# CrowPanel_ESP32_Display-5_0-inch-V3_0-20.net
KiCad netlist of a schematic drawn in EAGLE
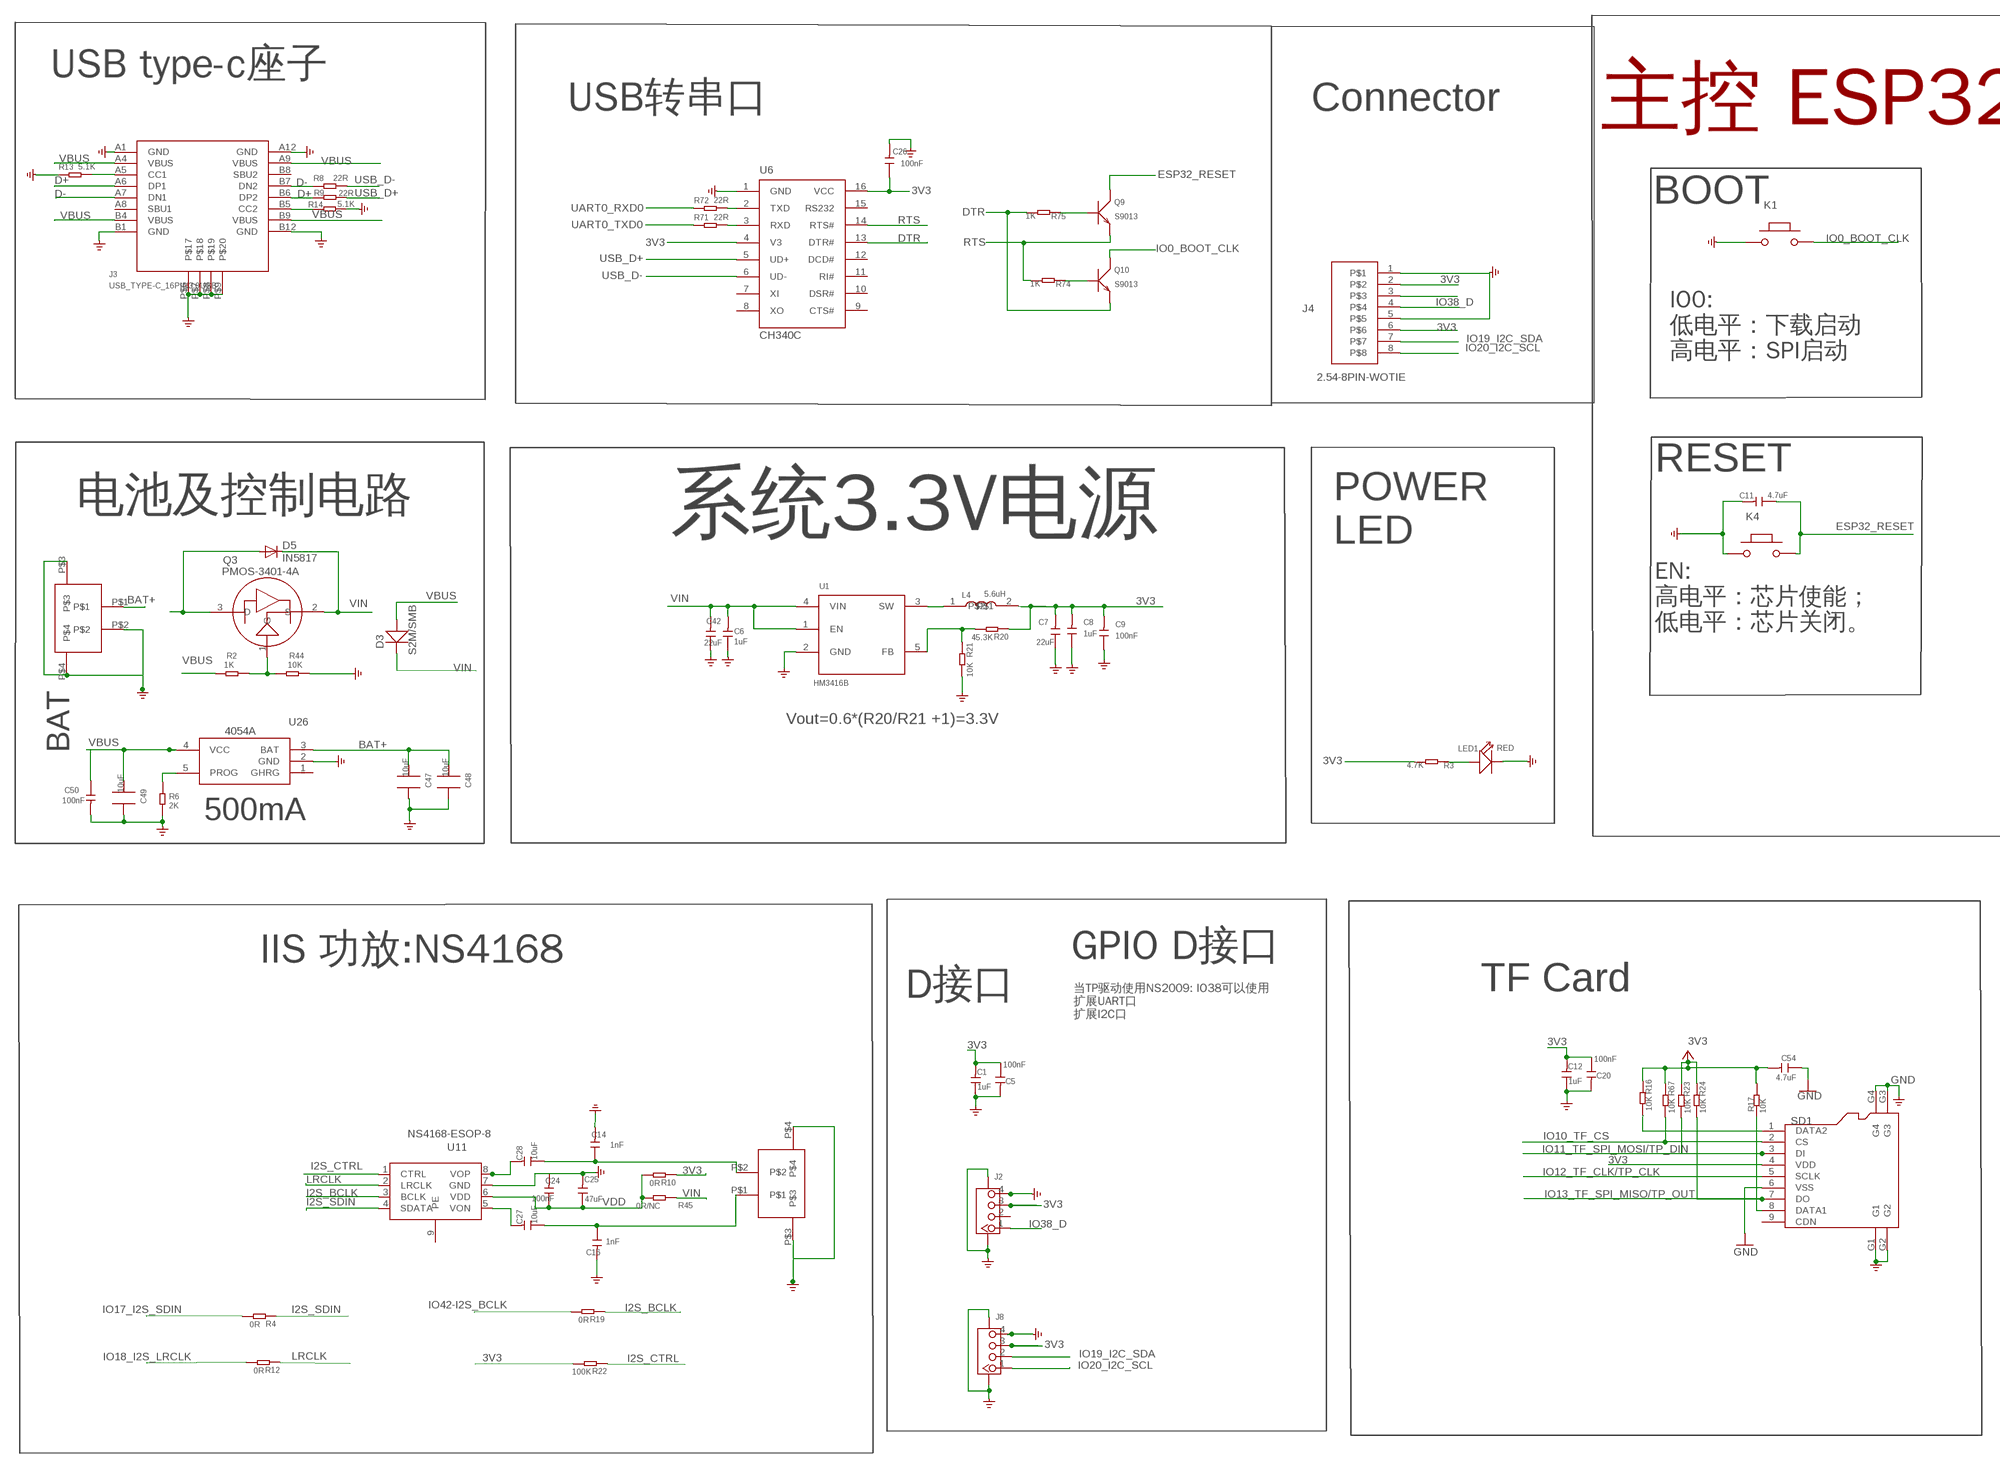
[diagram p0: schematic, sheet 1, part 1 of 2]
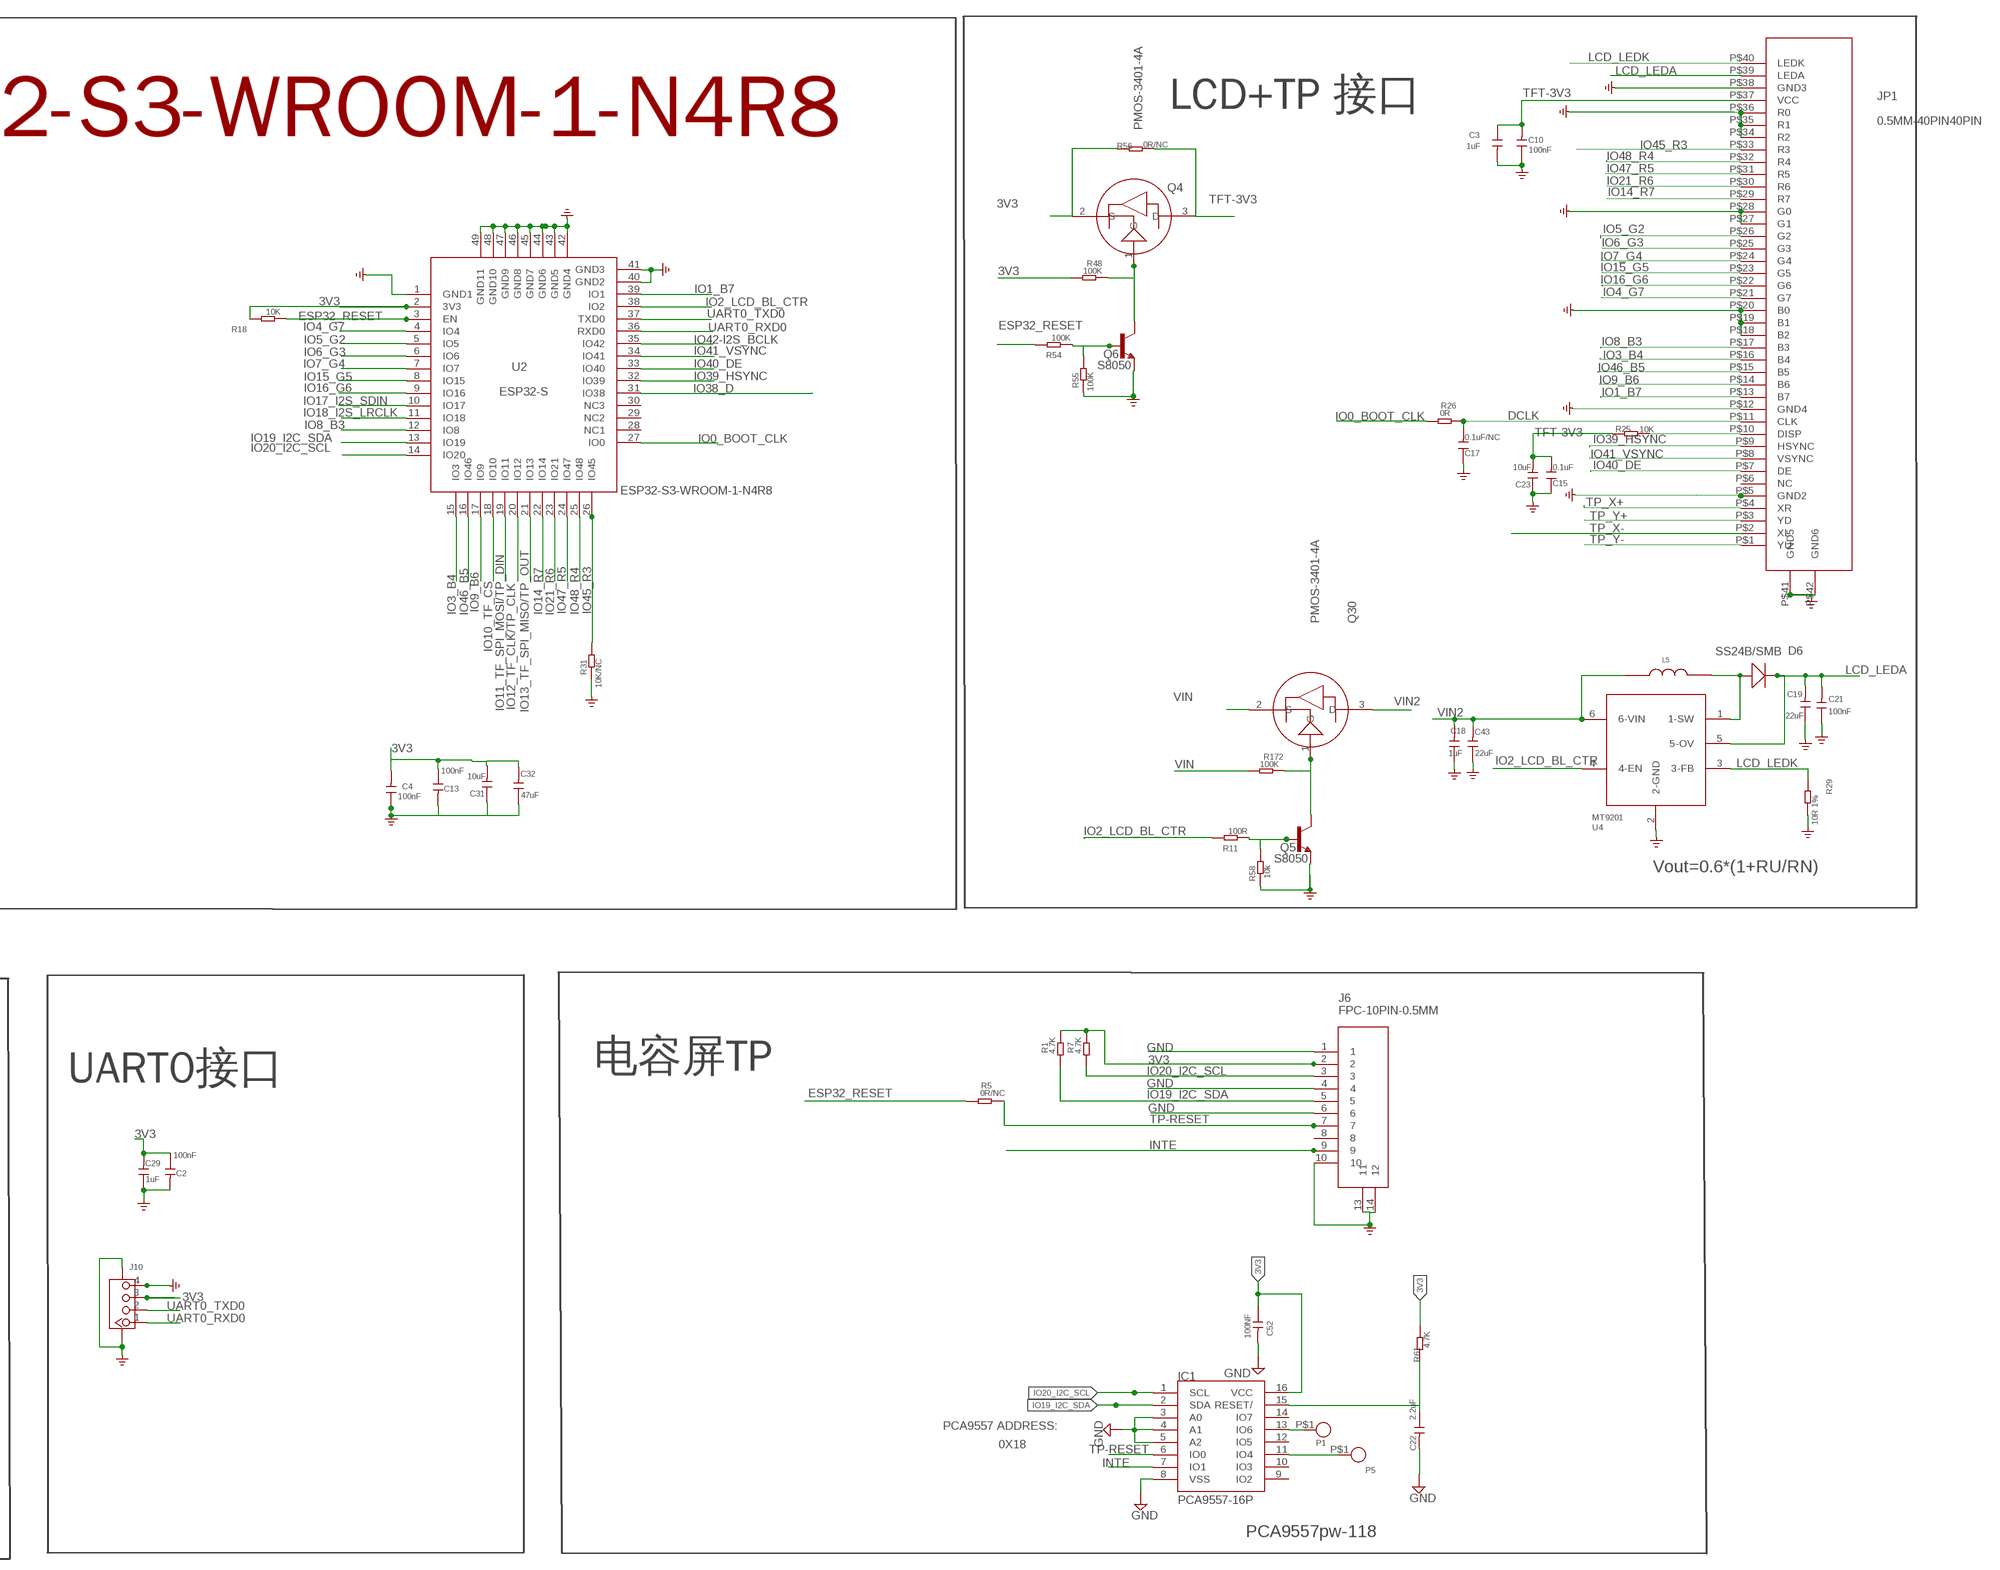
[diagram p1: schematic, sheet 1, part 2 of 2]

(export (version "E")
  (design (tool "Eeschema 10.0.6"))
  (components
    (comp (ref "C1")
      (value "1uF")
      (footprint "eagle-import:DISCRETE_C0603")
      (libsource (lib "eagle-import") (part "A_xbj_DISCRETE_C-0603"))
    )
    (comp (ref "C2")
      (value "100nF")
      (footprint "eagle-import:C0603")
      (libsource (lib "eagle-import") (part "C-0603"))
    )
    (comp (ref "C3")
      (value "1uF")
      (footprint "eagle-import:C0603")
      (libsource (lib "eagle-import") (part "C-0603"))
    )
    (comp (ref "C4")
      (value "100nF")
      (footprint "eagle-import:C0603")
      (libsource (lib "eagle-import") (part "C-0603"))
    )
    (comp (ref "C5")
      (value "100nF")
      (footprint "eagle-import:C0603")
      (libsource (lib "eagle-import") (part "C-0603"))
    )
    (comp (ref "C6")
      (value "1uF")
      (footprint "eagle-import:0603")
      (libsource (lib "eagle-import") (part "C0603"))
    )
    (comp (ref "C7")
      (value "22uF")
      (footprint "eagle-import:0805")
      (libsource (lib "eagle-import") (part "C0805"))
    )
    (comp (ref "C8")
      (value "1uF")
      (footprint "eagle-import:0603")
      (libsource (lib "eagle-import") (part "C0603"))
    )
    (comp (ref "C9")
      (value "100nF")
      (footprint "eagle-import:0603")
      (libsource (lib "eagle-import") (part "C0603"))
    )
    (comp (ref "C10")
      (value "100nF")
      (footprint "eagle-import:C0603")
      (libsource (lib "eagle-import") (part "C-0603"))
    )
    (comp (ref "C11")
      (value "4.7uF")
      (footprint "eagle-import:0603")
      (libsource (lib "eagle-import") (part "C0603"))
    )
    (comp (ref "C12")
      (value "1uF")
      (footprint "eagle-import:DISCRETE_C0603")
      (libsource (lib "eagle-import") (part "A_xbj_DISCRETE_C-0603"))
    )
    (comp (ref "C13")
      (value "100nF")
      (footprint "eagle-import:C0603")
      (libsource (lib "eagle-import") (part "C-0603"))
    )
    (comp (ref "C14")
      (value "1nF")
      (footprint "eagle-import:C0603")
      (libsource (lib "eagle-import") (part "C-0603"))
    )
    (comp (ref "C15")
      (value "0.1uF")
      (footprint "eagle-import:DISCRETE_C0603")
      (libsource (lib "eagle-import") (part "DISCRETE_C-0603"))
    )
    (comp (ref "C16")
      (value "1nF")
      (footprint "eagle-import:C0603")
      (libsource (lib "eagle-import") (part "C-0603"))
    )
    (comp (ref "C17")
      (value "0.1uF/NC")
      (footprint "eagle-import:DISCRETE_C0603")
      (libsource (lib "eagle-import") (part "DISCRETE_C-0603"))
    )
    (comp (ref "C18")
      (value "1uF")
      (footprint "eagle-import:0603")
      (libsource (lib "eagle-import") (part "C0603"))
    )
    (comp (ref "C19")
      (value "22uF")
      (footprint "eagle-import:0805")
      (libsource (lib "eagle-import") (part "C0805"))
    )
    (comp (ref "C20")
      (value "100nF")
      (footprint "eagle-import:C0603")
      (libsource (lib "eagle-import") (part "C-0603"))
    )
    (comp (ref "C21")
      (value "100nF")
      (footprint "eagle-import:0603")
      (libsource (lib "eagle-import") (part "C0603"))
    )
    (comp (ref "C22")
      (value "2.2uF")
      (footprint "eagle-import:0603")
      (libsource (lib "eagle-import") (part "C0603"))
    )
    (comp (ref "C23")
      (value "10uF")
      (footprint "eagle-import:DISCRETE_C0603")
      (libsource (lib "eagle-import") (part "DISCRETE_C-0603"))
    )
    (comp (ref "C24")
      (value "100nF")
      (footprint "eagle-import:C0603")
      (libsource (lib "eagle-import") (part "C-0603"))
    )
    (comp (ref "C25")
      (value "47uF")
      (footprint "eagle-import:0805")
      (libsource (lib "eagle-import") (part "C0805"))
    )
    (comp (ref "C26")
      (value "100nF")
      (footprint "eagle-import:0603")
      (libsource (lib "eagle-import") (part "C0603"))
    )
    (comp (ref "C27")
      (value "10uF")
      (footprint "eagle-import:DISCRETE_C0603")
      (libsource (lib "eagle-import") (part "A_xbj_DISCRETE_C-0603"))
    )
    (comp (ref "C28")
      (value "10uF")
      (footprint "eagle-import:DISCRETE_C0603")
      (libsource (lib "eagle-import") (part "A_xbj_DISCRETE_C-0603"))
    )
    (comp (ref "C29")
      (value "1uF")
      (footprint "eagle-import:DISCRETE_C0603")
      (libsource (lib "eagle-import") (part "A_xbj_DISCRETE_C-0603"))
    )
    (comp (ref "C31")
      (value "10uF")
      (footprint "eagle-import:DISCRETE_C0603")
      (libsource (lib "eagle-import") (part "DISCRETE_C-0603"))
    )
    (comp (ref "C32")
      (value "47uF")
      (footprint "eagle-import:0805")
      (libsource (lib "eagle-import") (part "C0805"))
    )
    (comp (ref "C42")
      (value "22uF")
      (footprint "eagle-import:0805")
      (libsource (lib "eagle-import") (part "C0805"))
    )
    (comp (ref "C43")
      (value "22uF")
      (footprint "eagle-import:0805")
      (libsource (lib "eagle-import") (part "C0805"))
    )
    (comp (ref "C47")
      (value "10uF")
      (footprint "eagle-import:0805_S")
      (libsource (lib "eagle-import") (part "C0805_S"))
    )
    (comp (ref "C48")
      (value "10uF")
      (footprint "eagle-import:0805_S")
      (libsource (lib "eagle-import") (part "C0805_S"))
    )
    (comp (ref "C49")
      (value "10uF")
      (footprint "eagle-import:0805_S")
      (libsource (lib "eagle-import") (part "C0805_S"))
    )
    (comp (ref "C50")
      (value "100nF")
      (footprint "eagle-import:C0603")
      (libsource (lib "eagle-import") (part "C-0603"))
    )
    (comp (ref "C52")
      (value "100NF")
      (footprint "eagle-import:A_XBJ_0603")
      (libsource (lib "eagle-import") (part "A_XBJ_C0603"))
    )
    (comp (ref "C54")
      (value "4.7uF")
      (footprint "eagle-import:DISCRETE_C0603")
      (libsource (lib "eagle-import") (part "DISCRETE_C-0603"))
    )
    (comp (ref "D3")
      (value "S2M/SMB")
      (footprint "eagle-import:214AB")
      (libsource (lib "eagle-import") (part "214ABDO-214AB"))
    )
    (comp (ref "D5")
      (value "IN5817")
      (footprint "eagle-import:DO-214AC")
      (libsource (lib "eagle-import") (part "DIODE-DO-214AC"))
    )
    (comp (ref "D6")
      (value "SS24B/SMB")
      (footprint "eagle-import:214AB")
      (libsource (lib "eagle-import") (part "214ABDO-214AB"))
    )
    (comp (ref "IC1")
      (value "PCA9557-16P")
      (footprint "eagle-import:TSSOP16")
      (libsource (lib "eagle-import") (part "PCA9557-16P"))
    )
    (comp (ref "J1")
      (value "PH2.0WT-2PIN")
      (footprint "eagle-import:PH2.0WT-2PIN")
      (libsource (lib "eagle-import") (part "PH2.0WT-2PIN"))
    )
    (comp (ref "J2")
      (value "CONNECTOR_TWIG-4P-2.0-SMD-FEMALE-REINFORCE90D")
      (footprint "eagle-import:CONNECTOR_4P-SMD-2.0-90D")
      (libsource (lib "eagle-import") (part "CONNECTOR_TWIG-4P-2.0-SMD-FEMALE-REINFORCE90D"))
    )
    (comp (ref "J3")
      (value "USB_TYPE-C_16PIN3.0USB")
      (footprint "eagle-import:KEVIN_3.0TYPEC-SMD")
      (libsource (lib "eagle-import") (part "USB_TYPE-C_16PIN3.0USB"))
    )
    (comp (ref "J4")
      (value "2.54-8PIN-WOTIE")
      (footprint "eagle-import:2.54-8P-WOTIE")
      (libsource (lib "eagle-import") (part "2.54-8PIN-WOTIE"))
    )
    (comp (ref "J5")
      (value "PH2.0WT-2PIN")
      (footprint "eagle-import:PH2.0WT-2PIN")
      (libsource (lib "eagle-import") (part "PH2.0WT-2PIN"))
    )
    (comp (ref "J6")
      (value "FPC-10PIN-0.5MM")
      (footprint "eagle-import:FPC-10PIN-0.5MM")
      (libsource (lib "eagle-import") (part "FPC-10PIN-0.5MM"))
    )
    (comp (ref "J8")
      (value "CONNECTOR_TWIG-4P-2.0-SMD-FEMALE-REINFORCE90D")
      (footprint "eagle-import:CONNECTOR_4P-SMD-2.0-90D")
      (libsource (lib "eagle-import") (part "CONNECTOR_TWIG-4P-2.0-SMD-FEMALE-REINFORCE90D"))
    )
    (comp (ref "J10")
      (value "CONNECTOR_TWIG-4P-2.0-SMD-FEMALE-REINFORCE90D")
      (footprint "eagle-import:CONNECTOR_4P-SMD-2.0-90D")
      (libsource (lib "eagle-import") (part "CONNECTOR_TWIG-4P-2.0-SMD-FEMALE-REINFORCE90D"))
    )
    (comp (ref "JP1")
      (value "0.5MM-40PIN40PIN")
      (footprint "eagle-import:0.5MM_40P")
      (libsource (lib "eagle-import") (part "0.5MM-40PIN40PIN"))
    )
    (comp (ref "K1")
      (value "BUTTON")
      (footprint "eagle-import:157SW")
      (libsource (lib "eagle-import") (part "PB157"))
    )
    (comp (ref "K4")
      (value "BUTTON")
      (footprint "eagle-import:157SW")
      (libsource (lib "eagle-import") (part "PB157"))
    )
    (comp (ref "L4")
      (value "5.6uH")
      (footprint "eagle-import:CD54_CD54")
      (libsource (lib "eagle-import") (part "L-0530"))
    )
    (comp (ref "L5")
      (value "CD32_6.8uH")
      (footprint "eagle-import:CD32")
      (libsource (lib "eagle-import") (part "CD32_950MA"))
    )
    (comp (ref "LED1")
      (value "RED")
      (footprint "eagle-import:DISCRETE_LED-0603")
      (libsource (lib "eagle-import") (part "DISCRETE_LED0603"))
    )
    (comp (ref "P1")
      (value "CROWPI_POW_PADPAD-1.0MM")
      (footprint "eagle-import:CROWPI_POW_PAD-1.0MM")
      (libsource (lib "eagle-import") (part "CROWPI_POW_PADPAD-1.0MM"))
    )
    (comp (ref "P5")
      (value "CROWPI_POW_PADPAD-1.0MM")
      (footprint "eagle-import:CROWPI_POW_PAD-1.0MM")
      (libsource (lib "eagle-import") (part "CROWPI_POW_PADPAD-1.0MM"))
    )
    (comp (ref "Q3")
      (value "PMOS-3401-4A")
      (footprint "eagle-import:SOT-23")
      (libsource (lib "eagle-import") (part "P-MOS-SOT23"))
    )
    (comp (ref "Q4")
      (value "PMOS-3401-4A")
      (footprint "eagle-import:SOT-23")
      (libsource (lib "eagle-import") (part "P-MOS-SOT23"))
    )
    (comp (ref "Q5")
      (value "S8050")
      (footprint "eagle-import:SPARKFUN_SOT23")
      (libsource (lib "eagle-import") (part "SPARKFUN_TRANSISTOR_NPNSOT23"))
    )
    (comp (ref "Q6")
      (value "S8050")
      (footprint "eagle-import:SPARKFUN_SOT23")
      (libsource (lib "eagle-import") (part "SPARKFUN_TRANSISTOR_NPNSOT23"))
    )
    (comp (ref "Q9")
      (value "S9013")
      (footprint "eagle-import:SOT23@1")
      (libsource (lib "eagle-import") (part "TRANSISTOR-NPN-SOT23"))
    )
    (comp (ref "Q10")
      (value "S9013")
      (footprint "eagle-import:SOT23@1")
      (libsource (lib "eagle-import") (part "TRANSISTOR-NPN-SOT23"))
    )
    (comp (ref "Q30")
      (value "PMOS-3401-4A")
      (footprint "eagle-import:SOT-23")
      (libsource (lib "eagle-import") (part "P-MOS-SOT23"))
    )
    (comp (ref "R1")
      (value "4.7K")
      (footprint "eagle-import:R0603")
      (libsource (lib "eagle-import") (part "R-0603"))
    )
    (comp (ref "R2")
      (value "1K")
      (footprint "eagle-import:DISCRETE_R0603")
      (libsource (lib "eagle-import") (part "DISCRETE_R-0603"))
    )
    (comp (ref "R3")
      (value "4.7K")
      (footprint "eagle-import:DISCRETE_R0603")
      (libsource (lib "eagle-import") (part "Crowtail-_LED-V2.0-20190615-01_DISCRETE_R-0603"))
    )
    (comp (ref "R4")
      (value "0R")
      (footprint "eagle-import:DISCRETE_R0603")
      (libsource (lib "eagle-import") (part "Crowtail-_LED-V2.0-20190615-01_DISCRETE_R-0603"))
    )
    (comp (ref "R5")
      (value "0R/NC")
      (footprint "eagle-import:R0603")
      (libsource (lib "eagle-import") (part "R-0603"))
    )
    (comp (ref "R6")
      (value "2K")
      (footprint "eagle-import:DISCRETE_R0603")
      (libsource (lib "eagle-import") (part "DISCRETE_R-0603"))
    )
    (comp (ref "R7")
      (value "4.7K")
      (footprint "eagle-import:R0603")
      (libsource (lib "eagle-import") (part "R-0603"))
    )
    (comp (ref "R8")
      (value "22R")
      (footprint "eagle-import:DISCRETE_R0603")
      (libsource (lib "eagle-import") (part "Crowtail-_LED-V2.0-20190615-01_DISCRETE_R-0603"))
    )
    (comp (ref "R9")
      (value "22R")
      (footprint "eagle-import:DISCRETE_R0603")
      (libsource (lib "eagle-import") (part "Crowtail-_LED-V2.0-20190615-01_DISCRETE_R-0603"))
    )
    (comp (ref "R10")
      (value "0R")
      (footprint "eagle-import:DISCRETE_R0603")
      (libsource (lib "eagle-import") (part "Crowtail-_LED-V2.0-20190615-01_DISCRETE_R-0603"))
    )
    (comp (ref "R11")
      (value "100R")
      (footprint "eagle-import:R0603")
      (libsource (lib "eagle-import") (part "R0603"))
    )
    (comp (ref "R12")
      (value "0R")
      (footprint "eagle-import:DISCRETE_R0603")
      (libsource (lib "eagle-import") (part "Crowtail-_LED-V2.0-20190615-01_DISCRETE_R-0603"))
    )
    (comp (ref "R13")
      (value "5.1K")
      (footprint "eagle-import:DISCRETE_R0603")
      (libsource (lib "eagle-import") (part "Crowtail-_LED-V2.0-20190615-01_DISCRETE_R-0603"))
    )
    (comp (ref "R14")
      (value "5.1K")
      (footprint "eagle-import:DISCRETE_R0603")
      (libsource (lib "eagle-import") (part "Crowtail-_LED-V2.0-20190615-01_DISCRETE_R-0603"))
    )
    (comp (ref "R16")
      (value "10K")
      (footprint "eagle-import:DISCRETE_R0603")
      (libsource (lib "eagle-import") (part "Crowtail-_LED-V2.0-20190615-01_DISCRETE_R-0603"))
    )
    (comp (ref "R17")
      (value "10K")
      (footprint "eagle-import:DISCRETE_R0603")
      (libsource (lib "eagle-import") (part "Crowtail-_LED-V2.0-20190615-01_DISCRETE_R-0603"))
    )
    (comp (ref "R18")
      (value "10K")
      (footprint "eagle-import:DISCRETE_R0603")
      (libsource (lib "eagle-import") (part "Crowtail-_LED-V2.0-20190615-01_DISCRETE_R-0603"))
    )
    (comp (ref "R19")
      (value "0R")
      (footprint "eagle-import:DISCRETE_R0603")
      (libsource (lib "eagle-import") (part "Crowtail-_LED-V2.0-20190615-01_DISCRETE_R-0603"))
    )
    (comp (ref "R20")
      (value "45.3K")
      (footprint "eagle-import:DISCRETE_R0603")
      (libsource (lib "eagle-import") (part "Crowtail-_LED-V2.0-20190615-01_DISCRETE_R-0603"))
    )
    (comp (ref "R21")
      (value "10K")
      (footprint "eagle-import:DISCRETE_R0603")
      (libsource (lib "eagle-import") (part "Crowtail-_LED-V2.0-20190615-01_DISCRETE_R-0603"))
    )
    (comp (ref "R22")
      (value "100K")
      (footprint "eagle-import:DISCRETE_R0603")
      (libsource (lib "eagle-import") (part "Crowtail-_LED-V2.0-20190615-01_DISCRETE_R-0603"))
    )
    (comp (ref "R23")
      (value "10K")
      (footprint "eagle-import:DISCRETE_R0603")
      (libsource (lib "eagle-import") (part "Crowtail-_LED-V2.0-20190615-01_DISCRETE_R-0603"))
    )
    (comp (ref "R24")
      (value "10K")
      (footprint "eagle-import:DISCRETE_R0603")
      (libsource (lib "eagle-import") (part "Crowtail-_LED-V2.0-20190615-01_DISCRETE_R-0603"))
    )
    (comp (ref "R25")
      (value "10K")
      (footprint "eagle-import:DISCRETE_R0603")
      (libsource (lib "eagle-import") (part "Crowtail-_LED-V2.0-20190615-01_DISCRETE_R-0603"))
    )
    (comp (ref "R26")
      (value "0R")
      (footprint "eagle-import:R0603")
      (libsource (lib "eagle-import") (part "R-0603"))
    )
    (comp (ref "R29")
      (value "10R 1%")
      (footprint "eagle-import:DISCRETE_R0603")
      (libsource (lib "eagle-import") (part "Crowtail-_LED-V2.0-20190615-01_DISCRETE_R-0603"))
    )
    (comp (ref "R31")
      (value "10K/NC")
      (footprint "eagle-import:R0603")
      (libsource (lib "eagle-import") (part "R0603"))
    )
    (comp (ref "R44")
      (value "10K")
      (footprint "eagle-import:DISCRETE_R0603")
      (libsource (lib "eagle-import") (part "DISCRETE_R-0603"))
    )
    (comp (ref "R45")
      (value "0R/NC")
      (footprint "eagle-import:DISCRETE_R0603")
      (libsource (lib "eagle-import") (part "Crowtail-_LED-V2.0-20190615-01_DISCRETE_R-0603"))
    )
    (comp (ref "R48")
      (value "100K")
      (footprint "eagle-import:R0603")
      (libsource (lib "eagle-import") (part "R-0603"))
    )
    (comp (ref "R54")
      (value "100K")
      (footprint "eagle-import:R0603")
      (libsource (lib "eagle-import") (part "R0603"))
    )
    (comp (ref "R55")
      (value "100K")
      (footprint "eagle-import:R0603")
      (libsource (lib "eagle-import") (part "R0603"))
    )
    (comp (ref "R56")
      (value "0R/NC")
      (footprint "eagle-import:DISCRETE_R0603")
      (libsource (lib "eagle-import") (part "Crowtail-_LED-V2.0-20190615-01_DISCRETE_R-0603"))
    )
    (comp (ref "R58")
      (value "10k")
      (footprint "eagle-import:R0603")
      (libsource (lib "eagle-import") (part "R0603"))
    )
    (comp (ref "R61")
      (value "4.7K")
      (footprint "eagle-import:DISCRETE_R0603")
      (libsource (lib "eagle-import") (part "Lora_RA-08H_Dev_DISCRETE_R-0603"))
    )
    (comp (ref "R67")
      (value "10K")
      (footprint "eagle-import:DISCRETE_R0603")
      (libsource (lib "eagle-import") (part "Crowtail-_LED-V2.0-20190615-01_DISCRETE_R-0603"))
    )
    (comp (ref "R71")
      (value "22R")
      (footprint "eagle-import:DISCRETE_R0603")
      (libsource (lib "eagle-import") (part "Crowtail-_LED-V2.0-20190615-01_DISCRETE_R-0603"))
    )
    (comp (ref "R72")
      (value "22R")
      (footprint "eagle-import:DISCRETE_R0603")
      (libsource (lib "eagle-import") (part "Crowtail-_LED-V2.0-20190615-01_DISCRETE_R-0603"))
    )
    (comp (ref "R74")
      (value "1K")
      (footprint "eagle-import:DISCRETE_R0603")
      (libsource (lib "eagle-import") (part "Crowtail-_LED-V2.0-20190615-01_DISCRETE_R-0603"))
    )
    (comp (ref "R75")
      (value "1K")
      (footprint "eagle-import:DISCRETE_R0603")
      (libsource (lib "eagle-import") (part "Crowtail-_LED-V2.0-20190615-01_DISCRETE_R-0603"))
    )
    (comp (ref "R172")
      (value "100K")
      (footprint "eagle-import:R0603")
      (libsource (lib "eagle-import") (part "R-0603"))
    )
    (comp (ref "SD1")
      (value "HOLDER-MICROSD-9P")
      (footprint "eagle-import:9P-SMD-W_-RING")
      (libsource (lib "eagle-import") (part "HOLDER-MICROSD-9P"))
    )
    (comp (ref "U1")
      (value "HM3416B")
      (footprint "eagle-import:A_XBJ_SOT23-5")
      (libsource (lib "eagle-import") (part "A_XBJ_HM3420B"))
    )
    (comp (ref "U2")
      (value "ESP32-S")
      (footprint "eagle-import:ESP32-S3")
      (fields (field (name "U2") "ESP32-S3-WROOM-1-N4R8"))
      (libsource (lib "eagle-import") (part "ESP32-S"))
    )
    (comp (ref "U4")
      (value "MT9201")
      (footprint "eagle-import:SOT23-6")
      (libsource (lib "eagle-import") (part "MT9201"))
    )
    (comp (ref "U6")
      (value "CH340C")
      (footprint "eagle-import:SOP-16")
      (libsource (lib "eagle-import") (part "CH340G"))
    )
    (comp (ref "U11")
      (value "NS4168-ESOP-8")
      (footprint "eagle-import:NS4168-ESOP-8")
      (libsource (lib "eagle-import") (part "NS4168-ESOP-8"))
    )
    (comp (ref "U26")
      (value "4054A")
      (footprint "eagle-import:SOP23-5")
      (libsource (lib "eagle-import") (part "4054A"))
    )
  )
  (nets
    (net (code "1") (name "/BAT+") (class "Default")
      (node (ref "C47") (pin "2") (pinfunction "2_2") (pintype "bidirectional"))
      (node (ref "C48") (pin "2") (pinfunction "2_2") (pintype "bidirectional"))
      (node (ref "D5") (pin "A") (pinfunction "A_A") (pintype "passive"))
      (node (ref "J1") (pin "P$1") (pinfunction "P$1_P$1") (pintype "bidirectional"))
      (node (ref "Q3") (pin "3") (pinfunction "D_3") (pintype "bidirectional"))
      (node (ref "U26") (pin "3") (pinfunction "BAT_3") (pintype "bidirectional"))
    )
    (net (code "2") (name "/D+") (class "Default")
      (node (ref "J3") (pin "A6") (pinfunction "DP1_A6") (pintype "bidirectional"))
      (node (ref "J3") (pin "B6") (pinfunction "DP2_B6") (pintype "bidirectional"))
      (node (ref "R9") (pin "1") (pinfunction "1_1") (pintype "passive"))
    )
    (net (code "3") (name "/D-") (class "Default")
      (node (ref "J3") (pin "A7") (pinfunction "DN1_A7") (pintype "bidirectional"))
      (node (ref "J3") (pin "B7") (pinfunction "DN2_B7") (pintype "bidirectional"))
      (node (ref "R8") (pin "1") (pinfunction "1_1") (pintype "passive"))
    )
    (net (code "4") (name "/DCLK") (class "Default")
      (node (ref "C17") (pin "2") (pinfunction "2_2") (pintype "passive"))
      (node (ref "JP1") (pin "P$11") (pinfunction "CLK_P$11") (pintype "bidirectional"))
      (node (ref "R26") (pin "2") (pinfunction "2_2") (pintype "passive"))
    )
    (net (code "5") (name "/DTR") (class "Default")
      (node (ref "Q10") (pin "2") (pinfunction "E_2") (pintype "passive"))
      (node (ref "R75") (pin "2") (pinfunction "2_2") (pintype "passive"))
      (node (ref "U6") (pin "13") (pinfunction "DTR#_13") (pintype "bidirectional"))
    )
    (net (code "6") (name "/ESP32_RESET") (class "Default")
      (node (ref "C11") (pin "1") (pinfunction "1_1") (pintype "passive"))
      (node (ref "K4") (pin "2") (pinfunction "2_2") (pintype "passive"))
      (node (ref "Q9") (pin "3") (pinfunction "C_3") (pintype "passive"))
      (node (ref "R18") (pin "2") (pinfunction "2_2") (pintype "passive"))
      (node (ref "R5") (pin "1") (pinfunction "1_1") (pintype "passive"))
      (node (ref "R54") (pin "2") (pinfunction "2_2") (pintype "passive"))
      (node (ref "U2") (pin "3") (pinfunction "EN_3") (pintype "bidirectional"))
    )
    (net (code "7") (name "/I2S_BCLK") (class "Default")
      (node (ref "R19") (pin "1") (pinfunction "1_1") (pintype "passive"))
      (node (ref "U11") (pin "3") (pinfunction "BCLK_3") (pintype "bidirectional"))
    )
    (net (code "8") (name "/I2S_CTRL") (class "Default")
      (node (ref "R22") (pin "1") (pinfunction "1_1") (pintype "passive"))
      (node (ref "U11") (pin "1") (pinfunction "CTRL_1") (pintype "bidirectional"))
    )
    (net (code "9") (name "/I2S_SDIN") (class "Default")
      (node (ref "R4") (pin "1") (pinfunction "1_1") (pintype "passive"))
      (node (ref "U11") (pin "4") (pinfunction "SDATA_4") (pintype "bidirectional"))
    )
    (net (code "10") (name "/INTE") (class "Default")
      (node (ref "IC1") (pin "7") (pinfunction "IO1_7") (pintype "bidirectional"))
      (node (ref "J6") (pin "9") (pinfunction "9_9") (pintype "bidirectional"))
    )
    (net (code "11") (name "/IO0_BOOT_CLK") (class "Default")
      (node (ref "K1") (pin "2") (pinfunction "2_2") (pintype "passive"))
      (node (ref "Q10") (pin "3") (pinfunction "C_3") (pintype "passive"))
      (node (ref "R26") (pin "1") (pinfunction "1_1") (pintype "passive"))
      (node (ref "U2") (pin "27") (pinfunction "IO0_27") (pintype "bidirectional"))
    )
    (net (code "12") (name "/IO1_B7") (class "Default")
      (node (ref "JP1") (pin "P$13") (pinfunction "B7_P$13") (pintype "bidirectional"))
      (node (ref "U2") (pin "39") (pinfunction "IO1_39") (pintype "bidirectional"))
    )
    (net (code "13") (name "/IO2_LCD_BL_CTR") (class "Default")
      (node (ref "R11") (pin "2") (pinfunction "2_2") (pintype "passive"))
      (node (ref "U2") (pin "38") (pinfunction "IO2_38") (pintype "bidirectional"))
      (node (ref "U4") (pin "4") (pinfunction "4-EN_4") (pintype "bidirectional"))
    )
    (net (code "14") (name "/IO3_B4") (class "Default")
      (node (ref "JP1") (pin "P$16") (pinfunction "B4_P$16") (pintype "bidirectional"))
      (node (ref "U2") (pin "15") (pinfunction "IO3_15") (pintype "bidirectional"))
    )
    (net (code "15") (name "/IO4_G7") (class "Default")
      (node (ref "JP1") (pin "P$21") (pinfunction "G7_P$21") (pintype "bidirectional"))
      (node (ref "U2") (pin "4") (pinfunction "IO4_4") (pintype "bidirectional"))
    )
    (net (code "16") (name "/IO5_G2") (class "Default")
      (node (ref "JP1") (pin "P$26") (pinfunction "G2_P$26") (pintype "bidirectional"))
      (node (ref "U2") (pin "5") (pinfunction "IO5_5") (pintype "bidirectional"))
    )
    (net (code "17") (name "/IO6_G3") (class "Default")
      (node (ref "JP1") (pin "P$25") (pinfunction "G3_P$25") (pintype "bidirectional"))
      (node (ref "U2") (pin "6") (pinfunction "IO6_6") (pintype "bidirectional"))
    )
    (net (code "18") (name "/IO7_G4") (class "Default")
      (node (ref "JP1") (pin "P$24") (pinfunction "G4_P$24") (pintype "bidirectional"))
      (node (ref "U2") (pin "7") (pinfunction "IO7_7") (pintype "bidirectional"))
    )
    (net (code "19") (name "/IO8_B3") (class "Default")
      (node (ref "JP1") (pin "P$17") (pinfunction "B3_P$17") (pintype "bidirectional"))
      (node (ref "U2") (pin "12") (pinfunction "IO8_12") (pintype "bidirectional"))
    )
    (net (code "20") (name "/IO9_B6") (class "Default")
      (node (ref "JP1") (pin "P$14") (pinfunction "B6_P$14") (pintype "bidirectional"))
      (node (ref "U2") (pin "17") (pinfunction "IO9_17") (pintype "bidirectional"))
    )
    (net (code "21") (name "/IO10_TF_CS") (class "Default")
      (node (ref "R67") (pin "2") (pinfunction "2_2") (pintype "passive"))
      (node (ref "SD1") (pin "2") (pinfunction "CS_2") (pintype "bidirectional"))
      (node (ref "U2") (pin "18") (pinfunction "IO10_18") (pintype "bidirectional"))
    )
    (net (code "22") (name "/IO11_TF_SPI_MOSI{slash}TP_DIN") (class "Default")
      (node (ref "R23") (pin "2") (pinfunction "2_2") (pintype "passive"))
      (node (ref "SD1") (pin "3") (pinfunction "DI_3") (pintype "bidirectional"))
      (node (ref "U2") (pin "19") (pinfunction "IO11_19") (pintype "bidirectional"))
    )
    (net (code "23") (name "/IO12_TF_CLK{slash}TP_CLK") (class "Default")
      (node (ref "SD1") (pin "5") (pinfunction "SCLK_5") (pintype "bidirectional"))
      (node (ref "U2") (pin "20") (pinfunction "IO12_20") (pintype "bidirectional"))
    )
    (net (code "24") (name "/IO13_TF_SPI_MISO{slash}TP_OUT") (class "Default")
      (node (ref "R24") (pin "2") (pinfunction "2_2") (pintype "passive"))
      (node (ref "SD1") (pin "7") (pinfunction "DO_7") (pintype "bidirectional"))
      (node (ref "U2") (pin "21") (pinfunction "IO13_21") (pintype "bidirectional"))
    )
    (net (code "25") (name "/IO14_R7") (class "Default")
      (node (ref "JP1") (pin "P$29") (pinfunction "R7_P$29") (pintype "bidirectional"))
      (node (ref "U2") (pin "22") (pinfunction "IO14_22") (pintype "bidirectional"))
    )
    (net (code "26") (name "/IO15_G5") (class "Default")
      (node (ref "JP1") (pin "P$23") (pinfunction "G5_P$23") (pintype "bidirectional"))
      (node (ref "U2") (pin "8") (pinfunction "IO15_8") (pintype "bidirectional"))
    )
    (net (code "27") (name "/IO16_G6") (class "Default")
      (node (ref "JP1") (pin "P$22") (pinfunction "G6_P$22") (pintype "bidirectional"))
      (node (ref "U2") (pin "9") (pinfunction "IO16_9") (pintype "bidirectional"))
    )
    (net (code "28") (name "/IO17_I2S_SDIN") (class "Default")
      (node (ref "R4") (pin "2") (pinfunction "2_2") (pintype "passive"))
      (node (ref "U2") (pin "10") (pinfunction "IO17_10") (pintype "bidirectional"))
    )
    (net (code "29") (name "/IO18_I2S_LRCLK") (class "Default")
      (node (ref "R12") (pin "2") (pinfunction "2_2") (pintype "passive"))
      (node (ref "U2") (pin "11") (pinfunction "IO18_11") (pintype "bidirectional"))
    )
    (net (code "30") (name "/IO21_R6") (class "Default")
      (node (ref "JP1") (pin "P$30") (pinfunction "R6_P$30") (pintype "bidirectional"))
      (node (ref "U2") (pin "23") (pinfunction "IO21_23") (pintype "bidirectional"))
    )
    (net (code "31") (name "/IO38_D") (class "Default")
      (node (ref "J2") (pin "1") (pinfunction "1_1") (pintype "bidirectional"))
      (node (ref "J4") (pin "4") (pinfunction "P$4_4") (pintype "bidirectional"))
      (node (ref "U2") (pin "31") (pinfunction "IO38_31") (pintype "bidirectional"))
    )
    (net (code "32") (name "/IO39_HSYNC") (class "Default")
      (node (ref "JP1") (pin "P$9") (pinfunction "HSYNC_P$9") (pintype "bidirectional"))
      (node (ref "U2") (pin "32") (pinfunction "IO39_32") (pintype "bidirectional"))
    )
    (net (code "33") (name "/IO40_DE") (class "Default")
      (node (ref "JP1") (pin "P$7") (pinfunction "DE_P$7") (pintype "bidirectional"))
      (node (ref "U2") (pin "33") (pinfunction "IO40_33") (pintype "bidirectional"))
    )
    (net (code "34") (name "/IO41_VSYNC") (class "Default")
      (node (ref "JP1") (pin "P$8") (pinfunction "VSYNC_P$8") (pintype "bidirectional"))
      (node (ref "U2") (pin "34") (pinfunction "IO41_34") (pintype "bidirectional"))
    )
    (net (code "35") (name "/IO42-I2S_BCLK") (class "Default")
      (node (ref "R19") (pin "2") (pinfunction "2_2") (pintype "passive"))
      (node (ref "U2") (pin "35") (pinfunction "IO42_35") (pintype "bidirectional"))
    )
    (net (code "36") (name "/IO45_R3") (class "Default")
      (node (ref "JP1") (pin "P$33") (pinfunction "R3_P$33") (pintype "bidirectional"))
      (node (ref "R31") (pin "2") (pinfunction "2_2") (pintype "passive"))
      (node (ref "U2") (pin "26") (pinfunction "IO45_26") (pintype "bidirectional"))
    )
    (net (code "37") (name "/IO46_B5") (class "Default")
      (node (ref "JP1") (pin "P$15") (pinfunction "B5_P$15") (pintype "bidirectional"))
      (node (ref "U2") (pin "16") (pinfunction "IO46_16") (pintype "bidirectional"))
    )
    (net (code "38") (name "/IO47_R5") (class "Default")
      (node (ref "JP1") (pin "P$31") (pinfunction "R5_P$31") (pintype "bidirectional"))
      (node (ref "U2") (pin "24") (pinfunction "IO47_24") (pintype "bidirectional"))
    )
    (net (code "39") (name "/IO48_R4") (class "Default")
      (node (ref "JP1") (pin "P$32") (pinfunction "R4_P$32") (pintype "bidirectional"))
      (node (ref "U2") (pin "25") (pinfunction "IO48_25") (pintype "bidirectional"))
    )
    (net (code "40") (name "/LCD_LEDA") (class "Default")
      (node (ref "C19") (pin "2") (pinfunction "2_2") (pintype "passive"))
      (node (ref "C21") (pin "2") (pinfunction "2_2") (pintype "passive"))
      (node (ref "D6") (pin "2") (pinfunction "-_2") (pintype "passive"))
      (node (ref "JP1") (pin "P$39") (pinfunction "LEDA_P$39") (pintype "bidirectional"))
      (node (ref "U4") (pin "5") (pinfunction "5-OV_5") (pintype "bidirectional"))
    )
    (net (code "41") (name "/LCD_LEDK") (class "Default")
      (node (ref "JP1") (pin "P$40") (pinfunction "LEDK_P$40") (pintype "bidirectional"))
      (node (ref "R29") (pin "1") (pinfunction "1_1") (pintype "passive"))
      (node (ref "U4") (pin "3") (pinfunction "3-FB_3") (pintype "bidirectional"))
    )
    (net (code "42") (name "/LRCLK") (class "Default")
      (node (ref "R12") (pin "1") (pinfunction "1_1") (pintype "passive"))
      (node (ref "U11") (pin "2") (pinfunction "LRCLK_2") (pintype "bidirectional"))
    )
    (net (code "43") (name "/RTS") (class "Default")
      (node (ref "Q9") (pin "2") (pinfunction "E_2") (pintype "passive"))
      (node (ref "R74") (pin "2") (pinfunction "2_2") (pintype "passive"))
      (node (ref "U6") (pin "14") (pinfunction "RTS#_14") (pintype "bidirectional"))
    )
    (net (code "44") (name "/TFT-3V3") (class "Default")
      (node (ref "C10") (pin "2") (pinfunction "2_2") (pintype "passive"))
      (node (ref "C15") (pin "2") (pinfunction "2_2") (pintype "passive"))
      (node (ref "C23") (pin "2") (pinfunction "2_2") (pintype "passive"))
      (node (ref "C3") (pin "1") (pinfunction "1_1") (pintype "passive"))
      (node (ref "JP1") (pin "P$37") (pinfunction "VCC_P$37") (pintype "bidirectional"))
      (node (ref "Q4") (pin "3") (pinfunction "D_3") (pintype "bidirectional"))
      (node (ref "R25") (pin "1") (pinfunction "1_1") (pintype "passive"))
      (node (ref "R56") (pin "2") (pinfunction "2_2") (pintype "passive"))
    )
    (net (code "45") (name "/TP-RESET") (class "Default")
      (node (ref "IC1") (pin "6") (pinfunction "IO0_6") (pintype "bidirectional"))
      (node (ref "J6") (pin "7") (pinfunction "7_7") (pintype "bidirectional"))
      (node (ref "R5") (pin "2") (pinfunction "2_2") (pintype "passive"))
    )
    (net (code "46") (name "/TP_X+") (class "Default")
      (node (ref "JP1") (pin "P$4") (pinfunction "XR_P$4") (pintype "bidirectional"))
    )
    (net (code "47") (name "/TP_X-") (class "Default")
      (node (ref "JP1") (pin "P$2") (pinfunction "XL_P$2") (pintype "bidirectional"))
    )
    (net (code "48") (name "/TP_Y+") (class "Default")
      (node (ref "JP1") (pin "P$3") (pinfunction "YD_P$3") (pintype "bidirectional"))
    )
    (net (code "49") (name "/TP_Y-") (class "Default")
      (node (ref "JP1") (pin "P$1") (pinfunction "YU_P$1") (pintype "bidirectional"))
    )
    (net (code "50") (name "/UART0_RXD0") (class "Default")
      (node (ref "J10") (pin "1") (pinfunction "1_1") (pintype "bidirectional"))
      (node (ref "R72") (pin "1") (pinfunction "1_1") (pintype "passive"))
      (node (ref "U2") (pin "36") (pinfunction "RXD0_36") (pintype "bidirectional"))
    )
    (net (code "51") (name "/UART0_TXD0") (class "Default")
      (node (ref "J10") (pin "2") (pinfunction "2_2") (pintype "bidirectional"))
      (node (ref "R71") (pin "1") (pinfunction "1_1") (pintype "passive"))
      (node (ref "U2") (pin "37") (pinfunction "TXD0_37") (pintype "bidirectional"))
    )
    (net (code "52") (name "/USB_D+") (class "Default")
      (node (ref "R9") (pin "2") (pinfunction "2_2") (pintype "passive"))
      (node (ref "U6") (pin "5") (pinfunction "UD+_5") (pintype "bidirectional"))
    )
    (net (code "53") (name "/USB_D-") (class "Default")
      (node (ref "R8") (pin "2") (pinfunction "2_2") (pintype "passive"))
      (node (ref "U6") (pin "6") (pinfunction "UD-_6") (pintype "bidirectional"))
    )
    (net (code "54") (name "/VBUS") (class "Default")
      (node (ref "C49") (pin "2") (pinfunction "2_2") (pintype "bidirectional"))
      (node (ref "C50") (pin "1") (pinfunction "1_1") (pintype "passive"))
      (node (ref "D3") (pin "1") (pinfunction "+_1") (pintype "passive"))
      (node (ref "J3") (pin "A4") (pinfunction "VBUS_A4") (pintype "bidirectional"))
      (node (ref "J3") (pin "A9") (pinfunction "VBUS_A9") (pintype "bidirectional"))
      (node (ref "J3") (pin "B4") (pinfunction "VBUS_B4") (pintype "bidirectional"))
      (node (ref "J3") (pin "B9") (pinfunction "VBUS_B9") (pintype "bidirectional"))
      (node (ref "R2") (pin "2") (pinfunction "2_2") (pintype "passive"))
      (node (ref "U26") (pin "4") (pinfunction "VCC_4") (pintype "bidirectional"))
    )
    (net (code "55") (name "/VDD") (class "Default")
      (node (ref "C24") (pin "1") (pinfunction "1_1") (pintype "passive"))
      (node (ref "C25") (pin "1") (pinfunction "1_1") (pintype "passive"))
      (node (ref "R10") (pin "2") (pinfunction "2_2") (pintype "passive"))
      (node (ref "R45") (pin "2") (pinfunction "2_2") (pintype "passive"))
      (node (ref "U11") (pin "6") (pinfunction "VDD_6") (pintype "bidirectional"))
    )
    (net (code "56") (name "/VIN") (class "Default")
      (node (ref "C42") (pin "2") (pinfunction "2_2") (pintype "passive"))
      (node (ref "C6") (pin "2") (pinfunction "2_2") (pintype "passive"))
      (node (ref "D3") (pin "2") (pinfunction "-_2") (pintype "passive"))
      (node (ref "D5") (pin "C") (pinfunction "C_C") (pintype "passive"))
      (node (ref "Q3") (pin "2") (pinfunction "S_2") (pintype "bidirectional"))
      (node (ref "Q30") (pin "2") (pinfunction "S_2") (pintype "bidirectional"))
      (node (ref "R172") (pin "1") (pinfunction "1_1") (pintype "passive"))
      (node (ref "R45") (pin "1") (pinfunction "1_1") (pintype "passive"))
      (node (ref "U1") (pin "1") (pinfunction "EN_1") (pintype "bidirectional"))
      (node (ref "U1") (pin "4") (pinfunction "VIN_4") (pintype "bidirectional"))
    )
    (net (code "57") (name "/VIN2") (class "Default")
      (node (ref "C18") (pin "2") (pinfunction "2_2") (pintype "passive"))
      (node (ref "C43") (pin "2") (pinfunction "2_2") (pintype "passive"))
      (node (ref "L5") (pin "1") (pinfunction "1_1") (pintype "bidirectional"))
      (node (ref "Q30") (pin "3") (pinfunction "D_3") (pintype "bidirectional"))
      (node (ref "U4") (pin "6") (pinfunction "6-VIN_6") (pintype "bidirectional"))
    )
    (net (code "58") (name "3V3") (class "Default")
      (node (ref "C1") (pin "2") (pinfunction "2_2") (pintype "passive"))
      (node (ref "C12") (pin "2") (pinfunction "2_2") (pintype "passive"))
      (node (ref "C13") (pin "1") (pinfunction "1_1") (pintype "passive"))
      (node (ref "C2") (pin "1") (pinfunction "1_1") (pintype "passive"))
      (node (ref "C20") (pin "1") (pinfunction "1_1") (pintype "passive"))
      (node (ref "C26") (pin "1") (pinfunction "1_1") (pintype "passive"))
      (node (ref "C29") (pin "2") (pinfunction "2_2") (pintype "passive"))
      (node (ref "C31") (pin "2") (pinfunction "2_2") (pintype "passive"))
      (node (ref "C32") (pin "2") (pinfunction "2_2") (pintype "passive"))
      (node (ref "C4") (pin "2") (pinfunction "2_2") (pintype "passive"))
      (node (ref "C5") (pin "1") (pinfunction "1_1") (pintype "passive"))
      (node (ref "C52") (pin "1") (pinfunction "1_1") (pintype "passive"))
      (node (ref "C54") (pin "2") (pinfunction "2_2") (pintype "passive"))
      (node (ref "C7") (pin "2") (pinfunction "2_2") (pintype "passive"))
      (node (ref "C8") (pin "2") (pinfunction "2_2") (pintype "passive"))
      (node (ref "C9") (pin "2") (pinfunction "2_2") (pintype "passive"))
      (node (ref "IC1") (pin "16") (pinfunction "VCC_16") (pintype "bidirectional"))
      (node (ref "J10") (pin "3") (pinfunction "3_3") (pintype "bidirectional"))
      (node (ref "J2") (pin "3") (pinfunction "3_3") (pintype "bidirectional"))
      (node (ref "J4") (pin "2") (pinfunction "P$2_2") (pintype "bidirectional"))
      (node (ref "J4") (pin "6") (pinfunction "P$6_6") (pintype "bidirectional"))
      (node (ref "J6") (pin "2") (pinfunction "2_2") (pintype "bidirectional"))
      (node (ref "J8") (pin "3") (pinfunction "3_3") (pintype "bidirectional"))
      (node (ref "L4") (pin "2") (pinfunction "P$2_2") (pintype "bidirectional"))
      (node (ref "Q4") (pin "2") (pinfunction "S_2") (pintype "bidirectional"))
      (node (ref "R1") (pin "2") (pinfunction "2_2") (pintype "passive"))
      (node (ref "R10") (pin "1") (pinfunction "1_1") (pintype "passive"))
      (node (ref "R16") (pin "1") (pinfunction "1_1") (pintype "passive"))
      (node (ref "R17") (pin "1") (pinfunction "1_1") (pintype "passive"))
      (node (ref "R18") (pin "1") (pinfunction "1_1") (pintype "passive"))
      (node (ref "R20") (pin "1") (pinfunction "1_1") (pintype "passive"))
      (node (ref "R22") (pin "2") (pinfunction "2_2") (pintype "passive"))
      (node (ref "R23") (pin "1") (pinfunction "1_1") (pintype "passive"))
      (node (ref "R24") (pin "1") (pinfunction "1_1") (pintype "passive"))
      (node (ref "R3") (pin "2") (pinfunction "2_2") (pintype "passive"))
      (node (ref "R48") (pin "1") (pinfunction "1_1") (pintype "passive"))
      (node (ref "R56") (pin "1") (pinfunction "1_1") (pintype "passive"))
      (node (ref "R61") (pin "2") (pinfunction "2_2") (pintype "passive"))
      (node (ref "R67") (pin "1") (pinfunction "1_1") (pintype "passive"))
      (node (ref "R7") (pin "2") (pinfunction "2_2") (pintype "passive"))
      (node (ref "SD1") (pin "4") (pinfunction "VDD_4") (pintype "bidirectional"))
      (node (ref "U2") (pin "2") (pinfunction "3V3_2") (pintype "bidirectional"))
      (node (ref "U6") (pin "16") (pinfunction "VCC_16") (pintype "bidirectional"))
      (node (ref "U6") (pin "4") (pinfunction "V3_4") (pintype "bidirectional"))
    )
    (net (code "59") (name "GND") (class "Default")
      (node (ref "C1") (pin "1") (pinfunction "1_1") (pintype "passive"))
      (node (ref "C10") (pin "1") (pinfunction "1_1") (pintype "passive"))
      (node (ref "C11") (pin "2") (pinfunction "2_2") (pintype "passive"))
      (node (ref "C12") (pin "1") (pinfunction "1_1") (pintype "passive"))
      (node (ref "C13") (pin "2") (pinfunction "2_2") (pintype "passive"))
      (node (ref "C14") (pin "2") (pinfunction "2_2") (pintype "passive"))
      (node (ref "C15") (pin "1") (pinfunction "1_1") (pintype "passive"))
      (node (ref "C16") (pin "2") (pinfunction "2_2") (pintype "passive"))
      (node (ref "C17") (pin "1") (pinfunction "1_1") (pintype "passive"))
      (node (ref "C18") (pin "1") (pinfunction "1_1") (pintype "passive"))
      (node (ref "C19") (pin "1") (pinfunction "1_1") (pintype "passive"))
      (node (ref "C2") (pin "2") (pinfunction "2_2") (pintype "passive"))
      (node (ref "C20") (pin "2") (pinfunction "2_2") (pintype "passive"))
      (node (ref "C21") (pin "1") (pinfunction "1_1") (pintype "passive"))
      (node (ref "C22") (pin "2") (pinfunction "2_2") (pintype "passive"))
      (node (ref "C23") (pin "1") (pinfunction "1_1") (pintype "passive"))
      (node (ref "C24") (pin "2") (pinfunction "2_2") (pintype "passive"))
      (node (ref "C25") (pin "2") (pinfunction "2_2") (pintype "passive"))
      (node (ref "C26") (pin "2") (pinfunction "2_2") (pintype "passive"))
      (node (ref "C29") (pin "1") (pinfunction "1_1") (pintype "passive"))
      (node (ref "C3") (pin "2") (pinfunction "2_2") (pintype "passive"))
      (node (ref "C31") (pin "1") (pinfunction "1_1") (pintype "passive"))
      (node (ref "C32") (pin "1") (pinfunction "1_1") (pintype "passive"))
      (node (ref "C4") (pin "1") (pinfunction "1_1") (pintype "passive"))
      (node (ref "C42") (pin "1") (pinfunction "1_1") (pintype "passive"))
      (node (ref "C43") (pin "1") (pinfunction "1_1") (pintype "passive"))
      (node (ref "C47") (pin "1") (pinfunction "1_1") (pintype "bidirectional"))
      (node (ref "C48") (pin "1") (pinfunction "1_1") (pintype "bidirectional"))
      (node (ref "C49") (pin "1") (pinfunction "1_1") (pintype "bidirectional"))
      (node (ref "C5") (pin "2") (pinfunction "2_2") (pintype "passive"))
      (node (ref "C50") (pin "2") (pinfunction "2_2") (pintype "passive"))
      (node (ref "C52") (pin "2") (pinfunction "2_2") (pintype "passive"))
      (node (ref "C54") (pin "1") (pinfunction "1_1") (pintype "passive"))
      (node (ref "C6") (pin "1") (pinfunction "1_1") (pintype "passive"))
      (node (ref "C7") (pin "1") (pinfunction "1_1") (pintype "passive"))
      (node (ref "C8") (pin "1") (pinfunction "1_1") (pintype "passive"))
      (node (ref "C9") (pin "1") (pinfunction "1_1") (pintype "passive"))
      (node (ref "IC1") (pin "3") (pinfunction "A0_3") (pintype "bidirectional"))
      (node (ref "IC1") (pin "4") (pinfunction "A1_4") (pintype "bidirectional"))
      (node (ref "IC1") (pin "5") (pinfunction "A2_5") (pintype "bidirectional"))
      (node (ref "IC1") (pin "8") (pinfunction "VSS_8") (pintype "bidirectional"))
      (node (ref "J1") (pin "P$2") (pinfunction "P$2_P$2") (pintype "bidirectional"))
      (node (ref "J1") (pin "P$3") (pinfunction "P$3_P$3") (pintype "bidirectional"))
      (node (ref "J1") (pin "P$4") (pinfunction "P$4_P$4") (pintype "bidirectional"))
      (node (ref "J10") (pin "4") (pinfunction "4_4") (pintype "bidirectional"))
      (node (ref "J10") (pin "SS1") (pinfunction "SS1_SS1") (pintype "bidirectional"))
      (node (ref "J10") (pin "SS2") (pinfunction "SS2_SS2") (pintype "bidirectional"))
      (node (ref "J2") (pin "4") (pinfunction "4_4") (pintype "bidirectional"))
      (node (ref "J2") (pin "SS1") (pinfunction "SS1_SS1") (pintype "bidirectional"))
      (node (ref "J2") (pin "SS2") (pinfunction "SS2_SS2") (pintype "bidirectional"))
      (node (ref "J3") (pin "A1") (pinfunction "GND_A1") (pintype "bidirectional"))
      (node (ref "J3") (pin "A12") (pinfunction "GND_A12") (pintype "bidirectional"))
      (node (ref "J3") (pin "B1") (pinfunction "GND_B1") (pintype "bidirectional"))
      (node (ref "J3") (pin "B12") (pinfunction "GND_B12") (pintype "bidirectional"))
      (node (ref "J3") (pin "P$6") (pinfunction "P$17_P$6") (pintype "bidirectional"))
      (node (ref "J3") (pin "P$7") (pinfunction "P$18_P$7") (pintype "bidirectional"))
      (node (ref "J3") (pin "P$8") (pinfunction "P$19_P$8") (pintype "bidirectional"))
      (node (ref "J3") (pin "P$9") (pinfunction "P$20_P$9") (pintype "bidirectional"))
      (node (ref "J4") (pin "1") (pinfunction "P$1_1") (pintype "bidirectional"))
      (node (ref "J4") (pin "5") (pinfunction "P$5_5") (pintype "bidirectional"))
      (node (ref "J5") (pin "P$3") (pinfunction "P$3_P$3") (pintype "bidirectional"))
      (node (ref "J5") (pin "P$4") (pinfunction "P$4_P$4") (pintype "bidirectional"))
      (node (ref "J6") (pin "1") (pinfunction "1_1") (pintype "bidirectional"))
      (node (ref "J6") (pin "10") (pinfunction "10_10") (pintype "bidirectional"))
      (node (ref "J6") (pin "13") (pinfunction "11_13") (pintype "bidirectional"))
      (node (ref "J6") (pin "14") (pinfunction "12_14") (pintype "bidirectional"))
      (node (ref "J6") (pin "4") (pinfunction "4_4") (pintype "bidirectional"))
      (node (ref "J6") (pin "6") (pinfunction "6_6") (pintype "bidirectional"))
      (node (ref "J8") (pin "4") (pinfunction "4_4") (pintype "bidirectional"))
      (node (ref "J8") (pin "SS1") (pinfunction "SS1_SS1") (pintype "bidirectional"))
      (node (ref "J8") (pin "SS2") (pinfunction "SS2_SS2") (pintype "bidirectional"))
      (node (ref "JP1") (pin "P$12") (pinfunction "GND4_P$12") (pintype "bidirectional"))
      (node (ref "JP1") (pin "P$18") (pinfunction "B2_P$18") (pintype "bidirectional"))
      (node (ref "JP1") (pin "P$19") (pinfunction "B1_P$19") (pintype "bidirectional"))
      (node (ref "JP1") (pin "P$20") (pinfunction "B0_P$20") (pintype "bidirectional"))
      (node (ref "JP1") (pin "P$27") (pinfunction "G1_P$27") (pintype "bidirectional"))
      (node (ref "JP1") (pin "P$28") (pinfunction "G0_P$28") (pintype "bidirectional"))
      (node (ref "JP1") (pin "P$34") (pinfunction "R2_P$34") (pintype "bidirectional"))
      (node (ref "JP1") (pin "P$35") (pinfunction "R1_P$35") (pintype "bidirectional"))
      (node (ref "JP1") (pin "P$36") (pinfunction "R0_P$36") (pintype "bidirectional"))
      (node (ref "JP1") (pin "P$38") (pinfunction "GND3_P$38") (pintype "bidirectional"))
      (node (ref "JP1") (pin "P$41") (pinfunction "GND5_P$41") (pintype "bidirectional"))
      (node (ref "JP1") (pin "P$42") (pinfunction "GND6_P$42") (pintype "bidirectional"))
      (node (ref "JP1") (pin "P$5") (pinfunction "GND2_P$5") (pintype "bidirectional"))
      (node (ref "K1") (pin "1") (pinfunction "1_1") (pintype "passive"))
      (node (ref "K4") (pin "1") (pinfunction "1_1") (pintype "passive"))
      (node (ref "LED1") (pin "-") (pinfunction "-_-") (pintype "passive"))
      (node (ref "Q5") (pin "2") (pinfunction "E_2") (pintype "passive"))
      (node (ref "Q6") (pin "2") (pinfunction "E_2") (pintype "passive"))
      (node (ref "R13") (pin "1") (pinfunction "1_1") (pintype "passive"))
      (node (ref "R14") (pin "2") (pinfunction "2_2") (pintype "passive"))
      (node (ref "R21") (pin "2") (pinfunction "2_2") (pintype "passive"))
      (node (ref "R29") (pin "2") (pinfunction "2_2") (pintype "passive"))
      (node (ref "R31") (pin "1") (pinfunction "1_1") (pintype "passive"))
      (node (ref "R44") (pin "1") (pinfunction "1_1") (pintype "passive"))
      (node (ref "R55") (pin "1") (pinfunction "1_1") (pintype "passive"))
      (node (ref "R58") (pin "1") (pinfunction "1_1") (pintype "passive"))
      (node (ref "R6") (pin "2") (pinfunction "2_2") (pintype "passive"))
      (node (ref "SD1") (pin "6") (pinfunction "VSS_6") (pintype "bidirectional"))
      (node (ref "SD1") (pin "G1") (pinfunction "G1_G1") (pintype "bidirectional"))
      (node (ref "SD1") (pin "G2") (pinfunction "G2_G2") (pintype "bidirectional"))
      (node (ref "SD1") (pin "G3") (pinfunction "G3_G3") (pintype "bidirectional"))
      (node (ref "SD1") (pin "G4") (pinfunction "G4_G4") (pintype "bidirectional"))
      (node (ref "U1") (pin "2") (pinfunction "GND_2") (pintype "bidirectional"))
      (node (ref "U11") (pin "7") (pinfunction "GND_7") (pintype "bidirectional"))
      (node (ref "U2") (pin "1") (pinfunction "GND1_1") (pintype "bidirectional"))
      (node (ref "U2") (pin "40") (pinfunction "GND2_40") (pintype "bidirectional"))
      (node (ref "U2") (pin "41") (pinfunction "GND3_41") (pintype "bidirectional"))
      (node (ref "U2") (pin "42") (pinfunction "GND4_42") (pintype "bidirectional"))
      (node (ref "U2") (pin "43") (pinfunction "GND5_43") (pintype "bidirectional"))
      (node (ref "U2") (pin "44") (pinfunction "GND6_44") (pintype "bidirectional"))
      (node (ref "U2") (pin "45") (pinfunction "GND7_45") (pintype "bidirectional"))
      (node (ref "U2") (pin "46") (pinfunction "GND8_46") (pintype "bidirectional"))
      (node (ref "U2") (pin "47") (pinfunction "GND9_47") (pintype "bidirectional"))
      (node (ref "U2") (pin "48") (pinfunction "GND10_48") (pintype "bidirectional"))
      (node (ref "U2") (pin "49") (pinfunction "GND11_49") (pintype "bidirectional"))
      (node (ref "U26") (pin "2") (pinfunction "GND_2") (pintype "bidirectional"))
      (node (ref "U4") (pin "2") (pinfunction "2-GND_2") (pintype "bidirectional"))
      (node (ref "U6") (pin "1") (pinfunction "GND_1") (pintype "bidirectional"))
    )
    (net (code "60") (name "IO19_I2C_SDA") (class "Default")
      (node (ref "IC1") (pin "2") (pinfunction "SDA_2") (pintype "bidirectional"))
      (node (ref "J4") (pin "7") (pinfunction "P$7_7") (pintype "bidirectional"))
      (node (ref "J6") (pin "5") (pinfunction "5_5") (pintype "bidirectional"))
      (node (ref "J8") (pin "2") (pinfunction "2_2") (pintype "bidirectional"))
      (node (ref "R1") (pin "1") (pinfunction "1_1") (pintype "passive"))
      (node (ref "U2") (pin "13") (pinfunction "IO19_13") (pintype "bidirectional"))
    )
    (net (code "61") (name "IO20_I2C_SCL") (class "Default")
      (node (ref "IC1") (pin "1") (pinfunction "SCL_1") (pintype "bidirectional"))
      (node (ref "J4") (pin "8") (pinfunction "P$8_8") (pintype "bidirectional"))
      (node (ref "J6") (pin "3") (pinfunction "3_3") (pintype "bidirectional"))
      (node (ref "J8") (pin "1") (pinfunction "1_1") (pintype "bidirectional"))
      (node (ref "R7") (pin "1") (pinfunction "1_1") (pintype "passive"))
      (node (ref "U2") (pin "14") (pinfunction "IO20_14") (pintype "bidirectional"))
    )
    (net (code "62") (name "Net-(C14-Pad1)") (class "Default")
      (node (ref "C14") (pin "1") (pinfunction "1_1") (pintype "passive"))
      (node (ref "C28") (pin "1") (pinfunction "1_1") (pintype "passive"))
      (node (ref "J5") (pin "P$2") (pinfunction "P$2_P$2") (pintype "bidirectional"))
    )
    (net (code "63") (name "Net-(C16-Pad1)") (class "Default")
      (node (ref "C16") (pin "1") (pinfunction "1_1") (pintype "passive"))
      (node (ref "C27") (pin "1") (pinfunction "1_1") (pintype "passive"))
      (node (ref "J5") (pin "P$1") (pinfunction "P$1_P$1") (pintype "bidirectional"))
    )
    (net (code "64") (name "Net-(D6-+)") (class "Default")
      (node (ref "D6") (pin "1") (pinfunction "+_1") (pintype "passive"))
      (node (ref "L5") (pin "2") (pinfunction "2_2") (pintype "bidirectional"))
      (node (ref "U4") (pin "1") (pinfunction "1-SW_1") (pintype "bidirectional"))
    )
    (net (code "65") (name "Net-(IC1-IO4)") (class "Default")
      (node (ref "IC1") (pin "11") (pinfunction "IO4_11") (pintype "bidirectional"))
      (node (ref "P5") (pin "P$1") (pinfunction "P$1_P$1") (pintype "bidirectional"))
    )
    (net (code "66") (name "Net-(IC1-IO6)") (class "Default")
      (node (ref "IC1") (pin "13") (pinfunction "IO6_13") (pintype "bidirectional"))
      (node (ref "P1") (pin "P$1") (pinfunction "P$1_P$1") (pintype "bidirectional"))
    )
    (net (code "67") (name "Net-(IC1-RESET{slash})") (class "Default")
      (node (ref "C22") (pin "1") (pinfunction "1_1") (pintype "passive"))
      (node (ref "IC1") (pin "15") (pinfunction "RESET/_15") (pintype "bidirectional"))
      (node (ref "R61") (pin "1") (pinfunction "1_1") (pintype "passive"))
    )
    (net (code "68") (name "Net-(J3-CC1)") (class "Default")
      (node (ref "J3") (pin "A5") (pinfunction "CC1_A5") (pintype "bidirectional"))
      (node (ref "R13") (pin "2") (pinfunction "2_2") (pintype "passive"))
    )
    (net (code "69") (name "Net-(J3-CC2)") (class "Default")
      (node (ref "J3") (pin "B5") (pinfunction "CC2_B5") (pintype "bidirectional"))
      (node (ref "R14") (pin "1") (pinfunction "1_1") (pintype "passive"))
    )
    (net (code "70") (name "Net-(JP1-DISP)") (class "Default")
      (node (ref "JP1") (pin "P$10") (pinfunction "DISP_P$10") (pintype "bidirectional"))
      (node (ref "R25") (pin "2") (pinfunction "2_2") (pintype "passive"))
    )
    (net (code "71") (name "Net-(L4-P$1)") (class "Default")
      (node (ref "L4") (pin "1") (pinfunction "P$1_1") (pintype "bidirectional"))
      (node (ref "U1") (pin "3") (pinfunction "SW_3") (pintype "bidirectional"))
    )
    (net (code "72") (name "Net-(LED1-Pad+)") (class "Default")
      (node (ref "LED1") (pin "+") (pinfunction "+_+") (pintype "passive"))
      (node (ref "R3") (pin "1") (pinfunction "1_1") (pintype "passive"))
    )
    (net (code "73") (name "Net-(Q3-G)") (class "Default")
      (node (ref "Q3") (pin "1") (pinfunction "G_1") (pintype "bidirectional"))
      (node (ref "R2") (pin "1") (pinfunction "1_1") (pintype "passive"))
      (node (ref "R44") (pin "2") (pinfunction "2_2") (pintype "passive"))
    )
    (net (code "74") (name "Net-(Q4-G)") (class "Default")
      (node (ref "Q4") (pin "1") (pinfunction "G_1") (pintype "bidirectional"))
      (node (ref "Q6") (pin "3") (pinfunction "C_3") (pintype "passive"))
      (node (ref "R48") (pin "2") (pinfunction "2_2") (pintype "passive"))
    )
    (net (code "75") (name "Net-(Q5-B)") (class "Default")
      (node (ref "Q5") (pin "1") (pinfunction "B_1") (pintype "passive"))
      (node (ref "R11") (pin "1") (pinfunction "1_1") (pintype "passive"))
      (node (ref "R58") (pin "2") (pinfunction "2_2") (pintype "passive"))
    )
    (net (code "76") (name "Net-(Q6-B)") (class "Default")
      (node (ref "Q6") (pin "1") (pinfunction "B_1") (pintype "passive"))
      (node (ref "R54") (pin "1") (pinfunction "1_1") (pintype "passive"))
      (node (ref "R55") (pin "2") (pinfunction "2_2") (pintype "passive"))
    )
    (net (code "77") (name "Net-(Q9-B)") (class "Default")
      (node (ref "Q9") (pin "1") (pinfunction "B_1") (pintype "passive"))
      (node (ref "R75") (pin "1") (pinfunction "1_1") (pintype "passive"))
    )
    (net (code "78") (name "Net-(Q10-B)") (class "Default")
      (node (ref "Q10") (pin "1") (pinfunction "B_1") (pintype "passive"))
      (node (ref "R74") (pin "1") (pinfunction "1_1") (pintype "passive"))
    )
    (net (code "79") (name "Net-(Q30-G)") (class "Default")
      (node (ref "Q30") (pin "1") (pinfunction "G_1") (pintype "bidirectional"))
      (node (ref "Q5") (pin "3") (pinfunction "C_3") (pintype "passive"))
      (node (ref "R172") (pin "2") (pinfunction "2_2") (pintype "passive"))
    )
    (net (code "80") (name "Net-(SD1-DATA1)") (class "Default")
      (node (ref "R17") (pin "2") (pinfunction "2_2") (pintype "passive"))
      (node (ref "SD1") (pin "8") (pinfunction "DATA1_8") (pintype "bidirectional"))
    )
    (net (code "81") (name "Net-(SD1-DATA2)") (class "Default")
      (node (ref "R16") (pin "2") (pinfunction "2_2") (pintype "passive"))
      (node (ref "SD1") (pin "1") (pinfunction "DATA2_1") (pintype "bidirectional"))
    )
    (net (code "82") (name "Net-(U1-FB)") (class "Default")
      (node (ref "R20") (pin "2") (pinfunction "2_2") (pintype "passive"))
      (node (ref "R21") (pin "1") (pinfunction "1_1") (pintype "passive"))
      (node (ref "U1") (pin "5") (pinfunction "FB_5") (pintype "bidirectional"))
    )
    (net (code "83") (name "Net-(U6-RXD)") (class "Default")
      (node (ref "R71") (pin "2") (pinfunction "2_2") (pintype "passive"))
      (node (ref "U6") (pin "3") (pinfunction "RXD_3") (pintype "bidirectional"))
    )
    (net (code "84") (name "Net-(U6-TXD)") (class "Default")
      (node (ref "R72") (pin "2") (pinfunction "2_2") (pintype "passive"))
      (node (ref "U6") (pin "2") (pinfunction "TXD_2") (pintype "bidirectional"))
    )
    (net (code "85") (name "Net-(U11-VON)") (class "Default")
      (node (ref "C27") (pin "2") (pinfunction "2_2") (pintype "passive"))
      (node (ref "U11") (pin "5") (pinfunction "VON_5") (pintype "bidirectional"))
    )
    (net (code "86") (name "Net-(U11-VOP)") (class "Default")
      (node (ref "C28") (pin "2") (pinfunction "2_2") (pintype "passive"))
      (node (ref "U11") (pin "8") (pinfunction "VOP_8") (pintype "bidirectional"))
    )
    (net (code "87") (name "Net-(U26-PROG)") (class "Default")
      (node (ref "R6") (pin "1") (pinfunction "1_1") (pintype "passive"))
      (node (ref "U26") (pin "5") (pinfunction "PROG_5") (pintype "bidirectional"))
    )
    (net (code "88") (name "unconnected-(IC1-IO2-Pad9)") (class "Default")
      (node (ref "IC1") (pin "9") (pinfunction "IO2_9") (pintype "bidirectional"))
    )
    (net (code "89") (name "unconnected-(IC1-IO3-Pad10)") (class "Default")
      (node (ref "IC1") (pin "10") (pinfunction "IO3_10") (pintype "bidirectional"))
    )
    (net (code "90") (name "unconnected-(IC1-IO5-Pad12)") (class "Default")
      (node (ref "IC1") (pin "12") (pinfunction "IO5_12") (pintype "bidirectional"))
    )
    (net (code "91") (name "unconnected-(IC1-IO7-Pad14)") (class "Default")
      (node (ref "IC1") (pin "14") (pinfunction "IO7_14") (pintype "bidirectional"))
    )
    (net (code "92") (name "unconnected-(J2-Pad2)") (class "Default")
      (node (ref "J2") (pin "2") (pinfunction "2_2") (pintype "bidirectional"))
    )
    (net (code "93") (name "unconnected-(J3-SBU1-PadA8)") (class "Default")
      (node (ref "J3") (pin "A8") (pinfunction "SBU1_A8") (pintype "bidirectional"))
    )
    (net (code "94") (name "unconnected-(J3-SBU2-PadB8)") (class "Default")
      (node (ref "J3") (pin "B8") (pinfunction "SBU2_B8") (pintype "bidirectional"))
    )
    (net (code "95") (name "unconnected-(J4-P$3-Pad3)") (class "Default")
      (node (ref "J4") (pin "3") (pinfunction "P$3_3") (pintype "bidirectional"))
    )
    (net (code "96") (name "unconnected-(J6-Pad8)") (class "Default")
      (node (ref "J6") (pin "8") (pinfunction "8_8") (pintype "bidirectional"))
    )
    (net (code "97") (name "unconnected-(JP1-NC-PadP$6)") (class "Default")
      (node (ref "JP1") (pin "P$6") (pinfunction "NC_P$6") (pintype "bidirectional"))
    )
    (net (code "98") (name "unconnected-(SD1-CDN-Pad9)") (class "Default")
      (node (ref "SD1") (pin "9") (pinfunction "CDN_9") (pintype "bidirectional"))
    )
    (net (code "99") (name "unconnected-(U2-NC1-Pad28)") (class "Default")
      (node (ref "U2") (pin "28") (pinfunction "NC1_28") (pintype "bidirectional"))
    )
    (net (code "100") (name "unconnected-(U2-NC2-Pad29)") (class "Default")
      (node (ref "U2") (pin "29") (pinfunction "NC2_29") (pintype "bidirectional"))
    )
    (net (code "101") (name "unconnected-(U2-NC3-Pad30)") (class "Default")
      (node (ref "U2") (pin "30") (pinfunction "NC3_30") (pintype "bidirectional"))
    )
    (net (code "102") (name "unconnected-(U6-CTS#-Pad9)") (class "Default")
      (node (ref "U6") (pin "9") (pinfunction "CTS#_9") (pintype "bidirectional"))
    )
    (net (code "103") (name "unconnected-(U6-DCD#-Pad12)") (class "Default")
      (node (ref "U6") (pin "12") (pinfunction "DCD#_12") (pintype "bidirectional"))
    )
    (net (code "104") (name "unconnected-(U6-DSR#-Pad10)") (class "Default")
      (node (ref "U6") (pin "10") (pinfunction "DSR#_10") (pintype "bidirectional"))
    )
    (net (code "105") (name "unconnected-(U6-RI#-Pad11)") (class "Default")
      (node (ref "U6") (pin "11") (pinfunction "RI#_11") (pintype "bidirectional"))
    )
    (net (code "106") (name "unconnected-(U6-RS232-Pad15)") (class "Default")
      (node (ref "U6") (pin "15") (pinfunction "RS232_15") (pintype "bidirectional"))
    )
    (net (code "107") (name "unconnected-(U6-XI-Pad7)") (class "Default")
      (node (ref "U6") (pin "7") (pinfunction "XI_7") (pintype "bidirectional"))
    )
    (net (code "108") (name "unconnected-(U6-XO-Pad8)") (class "Default")
      (node (ref "U6") (pin "8") (pinfunction "XO_8") (pintype "bidirectional"))
    )
    (net (code "109") (name "unconnected-(U11-PE-Pad9)") (class "Default")
      (node (ref "U11") (pin "9") (pinfunction "PE_9") (pintype "bidirectional"))
    )
    (net (code "110") (name "unconnected-(U26-GHRG-Pad1)") (class "Default")
      (node (ref "U26") (pin "1") (pinfunction "GHRG_1") (pintype "bidirectional"))
    )
  )
)
